# 02_LDO_and_LiPo_Circuit.net
KiCad netlist of a schematic drawn in Altium Designer
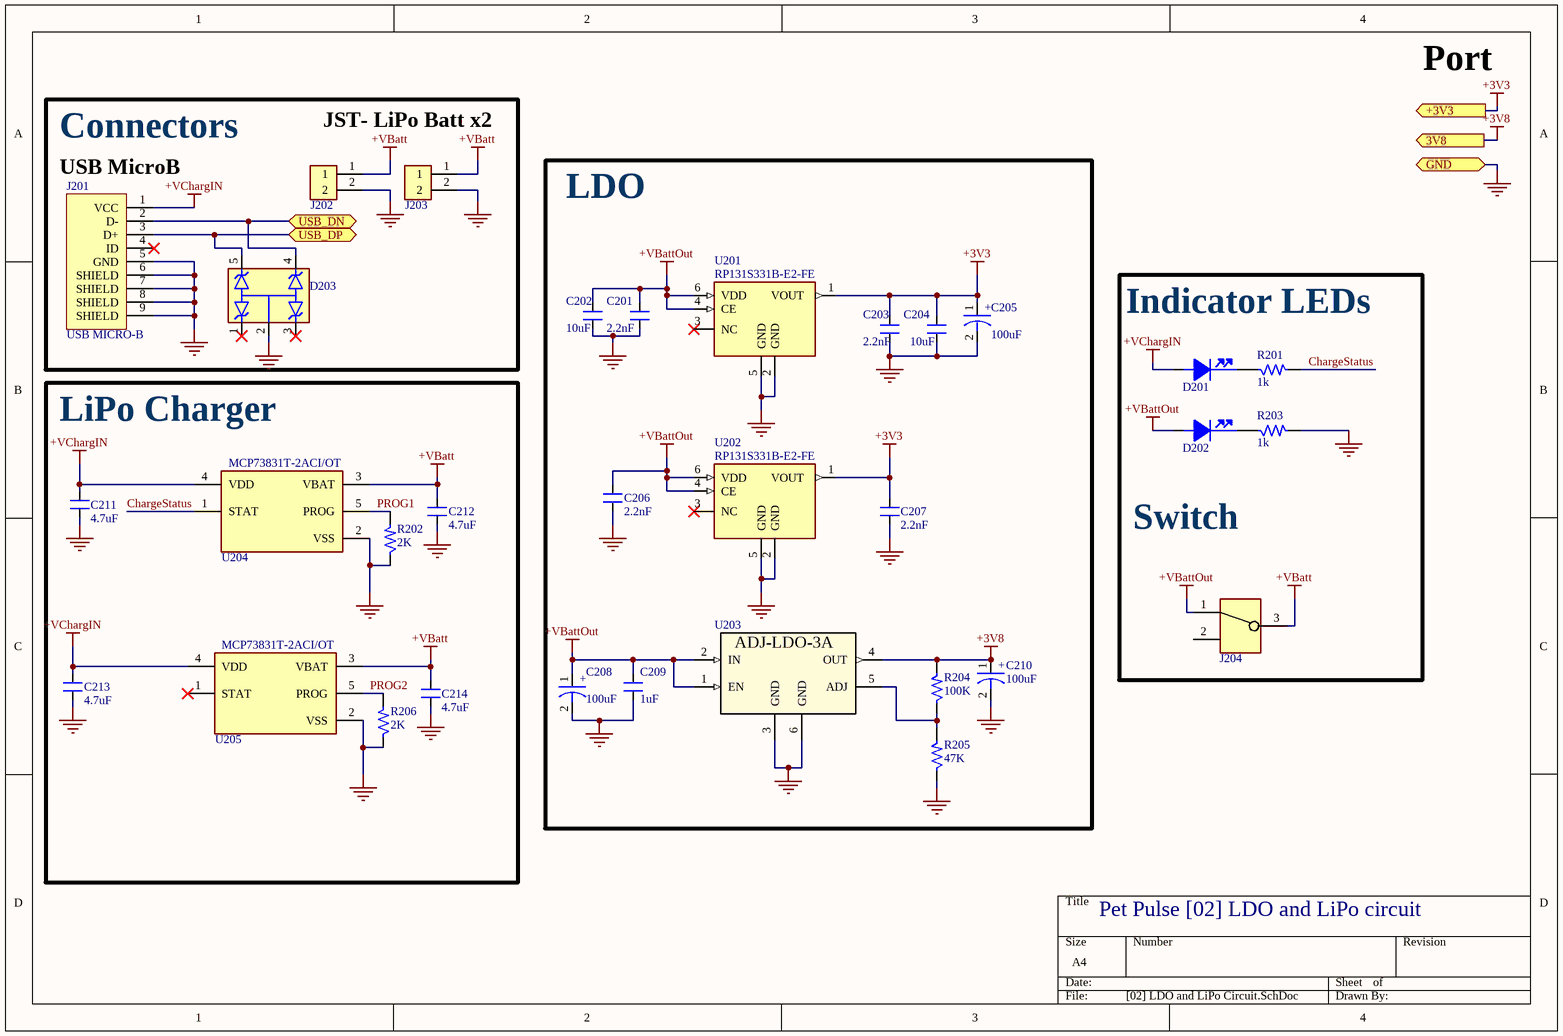
[diagram p0: [02] LDO and LiPo Circuit.SchDoc]

(export (version "E")
  (design (tool "Eeschema 10.0.6"))
  (components
    (comp (ref "C201")
      (value "2.2nF")
      (footprint "CAP_0805")
      (description "2200pF ±10% 50V Ceramic Capacitor C0G, NP0 0805 (2012 Metric)")
      (fields
        (field (name "MANUFACTURER") "YAGEO")
        (field (name "MANUFACTURER PART NUMBER") "CC0805KRX7R9BB222")
      )
      (libsource (lib "SchematicLibrary") (part "CAP_2.2nF-50V-10%-0805"))
    )
    (comp (ref "C202")
      (value "10uF")
      (footprint "CAP_1206")
      (description "10µF ±10% 50V Ceramic Capacitor X7R 1206 (3216 Metric)")
      (fields
        (field (name "MANUFACTURER") "KEMET")
        (field (name "MANUFACTURER PART NUMBER") "CL31B106KBHNNNE")
      )
      (libsource (lib "IntegratedLibraryNamanTanwar") (part "CAP_10uF-50V-10%-1206"))
    )
    (comp (ref "C203")
      (value "2.2nF")
      (footprint "CAP_0805")
      (description "2200pF ±10% 50V Ceramic Capacitor C0G, NP0 0805 (2012 Metric)")
      (fields
        (field (name "MANUFACTURER") "YAGEO")
        (field (name "MANUFACTURER PART NUMBER") "CC0805KRX7R9BB222")
      )
      (libsource (lib "SchematicLibrary") (part "CAP_2.2nF-50V-10%-0805"))
    )
    (comp (ref "C204")
      (value "10uF")
      (footprint "CAP_1206")
      (description "10µF ±10% 50V Ceramic Capacitor X7R 1206 (3216 Metric)")
      (fields
        (field (name "MANUFACTURER") "KEMET")
        (field (name "MANUFACTURER PART NUMBER") "CL31B106KBHNNNE")
      )
      (libsource (lib "IntegratedLibraryNamanTanwar") (part "CAP_10uF-50V-10%-1206"))
    )
    (comp (ref "C205")
      (value "100uF")
      (footprint "ACAP_P236_D305_H303_RAD")
      (description "100µF 25V Aluminum Electrolytic Capacitors Radial, Can - SMD 1000 Hrs @ 105°C")
      (fields
        (field (name "MANUFACTURER") "Nichicon")
        (field (name "MANUFACTURER PART NUMBER") "UWT1E101MCL1GS")
      )
      (libsource (lib "IntegratedLibraryNamanTanwar") (part "CAP-P_100uF-25V-20%-RAD"))
    )
    (comp (ref "C206")
      (value "2.2nF")
      (footprint "CAP_0805")
      (description "2200pF ±10% 50V Ceramic Capacitor C0G, NP0 0805 (2012 Metric)")
      (fields
        (field (name "MANUFACTURER") "YAGEO")
        (field (name "MANUFACTURER PART NUMBER") "CC0805KRX7R9BB222")
      )
      (libsource (lib "SchematicLibrary") (part "CAP_2.2nF-50V-10%-0805"))
    )
    (comp (ref "C207")
      (value "2.2nF")
      (footprint "CAP_0805")
      (description "2200pF ±10% 50V Ceramic Capacitor C0G, NP0 0805 (2012 Metric)")
      (fields
        (field (name "MANUFACTURER") "YAGEO")
        (field (name "MANUFACTURER PART NUMBER") "CC0805KRX7R9BB222")
      )
      (libsource (lib "SchematicLibrary") (part "CAP_2.2nF-50V-10%-0805"))
    )
    (comp (ref "C208")
      (value "100uF")
      (footprint "ACAP_P236_D305_H303_RAD")
      (description "100µF 25V Aluminum Electrolytic Capacitors Radial, Can - SMD 1000 Hrs @ 105°C")
      (fields
        (field (name "MANUFACTURER") "Nichicon")
        (field (name "MANUFACTURER PART NUMBER") "UWT1E101MCL1GS")
      )
      (libsource (lib "IntegratedLibraryNamanTanwar") (part "CAP-P_100uF-25V-20%-RAD"))
    )
    (comp (ref "C209")
      (value "1uF")
      (footprint "CAP_0805")
      (description "1µF ±5% 50V Ceramic Capacitor X7R 0805 (2012 Metric)")
      (fields
        (field (name "MANUFACTURER") "Samsung")
        (field (name "MANUFACTURER PART NUMBER") "CC0805JKX7R9BB105")
      )
      (libsource (lib "IntegratedLibraryNamanTanwar") (part "CAP_1uF-50V-5%-0805"))
    )
    (comp (ref "C210")
      (value "100uF")
      (footprint "ACAP_P236_D305_H303_RAD")
      (description "100µF 25V Aluminum Electrolytic Capacitors Radial, Can - SMD 1000 Hrs @ 105°C")
      (fields
        (field (name "MANUFACTURER") "Nichicon")
        (field (name "MANUFACTURER PART NUMBER") "UWT1E101MCL1GS")
      )
      (libsource (lib "IntegratedLibraryNamanTanwar") (part "CAP-P_100uF-25V-20%-RAD"))
    )
    (comp (ref "C211")
      (value "4.7uF")
      (footprint "CAP_0805")
      (description "4.7µF ±10% 50V Ceramic Capacitor X5R 0805 (2012 Metric)")
      (fields
        (field (name "MANUFACTURER") "Yageo")
        (field (name "MANUFACTURER PART NUMBER") "GRM21BR61H475KE51L")
      )
      (libsource (lib "IntegratedLibraryNamanTanwar") (part "CAP_4.7uF-50V-10%-0805"))
    )
    (comp (ref "C212")
      (value "4.7uF")
      (footprint "CAP_0805")
      (description "4.7µF ±10% 50V Ceramic Capacitor X5R 0805 (2012 Metric)")
      (fields
        (field (name "MANUFACTURER") "Yageo")
        (field (name "MANUFACTURER PART NUMBER") "GRM21BR61H475KE51L")
      )
      (libsource (lib "IntegratedLibraryNamanTanwar") (part "CAP_4.7uF-50V-10%-0805"))
    )
    (comp (ref "C213")
      (value "4.7uF")
      (footprint "CAP_0805")
      (description "4.7µF ±10% 50V Ceramic Capacitor X5R 0805 (2012 Metric)")
      (fields
        (field (name "MANUFACTURER") "Yageo")
        (field (name "MANUFACTURER PART NUMBER") "GRM21BR61H475KE51L")
      )
      (libsource (lib "IntegratedLibraryNamanTanwar") (part "CAP_4.7uF-50V-10%-0805"))
    )
    (comp (ref "C214")
      (value "4.7uF")
      (footprint "CAP_0805")
      (description "4.7µF ±10% 50V Ceramic Capacitor X5R 0805 (2012 Metric)")
      (fields
        (field (name "MANUFACTURER") "Yageo")
        (field (name "MANUFACTURER PART NUMBER") "GRM21BR61H475KE51L")
      )
      (libsource (lib "IntegratedLibraryNamanTanwar") (part "CAP_4.7uF-50V-10%-0805"))
    )
    (comp (ref "D201")
      (value "LED 0805 ORANGE")
      (footprint "LED_0805")
      (description "Orange LED 0805 Vf = 2V, 20mA")
      (fields
        (field (name "MANUFACTURER") "Osram Opto")
        (field (name "MANUFACTURER PART NUMBER") "LOR976-PS-1")
      )
      (libsource (lib "IntegratedLibraryNamanTanwar") (part "LED_ORANGE-2V-20mA- 0805"))
    )
    (comp (ref "D202")
      (value "LED 0805 ORANGE")
      (footprint "LED_0805")
      (description "Orange LED 0805 Vf = 2V, 20mA")
      (fields
        (field (name "MANUFACTURER") "Osram Opto")
        (field (name "MANUFACTURER PART NUMBER") "LOR976-PS-1")
      )
      (libsource (lib "IntegratedLibraryNamanTanwar") (part "LED_ORANGE-2V-20mA- 0805"))
    )
    (comp (ref "D203")
      (value "ESDA6V1W5")
      (footprint "SOT-323-5")
      (description "Tvs Diode Array 3V reverse standoff, 6.1V reverse breakdown.  SOT-323-5")
      (fields (field (name "MANUFACTURER") "STMicroelectronics"))
      (libsource (lib "IntegratedLibraryNamanTanwar") (part "DIO_TVS_ARRY_3Vrm_6.1Vbr_ESDA6V1W5"))
    )
    (comp (ref "J201")
      (value "USB MICRO-B")
      (footprint "CON_USB2.0_MICROB-SMD")
      (description "USB - micro B USB 2.0 Receptacle Connector 5 Position Surface Mount, Right Angle")
      (fields (field (name "MANUFACTURER") "ICC") (field (name "MANUFACTURER PART NUMBER") "10118192-0001LF"))
      (libsource (lib "IntegratedLibraryNamanTanwar") (part "CON_USB2.0_MICROB-SMD"))
    )
    (comp (ref "J202")
      (value "1x2 JST")
      (footprint "CON-JST-1X2-1.5-M-TH")
      (description "Connector Header Through Hole 2 position 0.059\" (1.50mm)")
      (fields
        (field (name "MANUFACTURER") "JST Sales America Inc.")
        (field (name "MANUFACTURER PART NUMBER") "B2B-ZR (LF)(SN)")
      )
      (libsource (lib "SchematicLibrary") (part "CON-JST-1X2-1.5-M-TH"))
    )
    (comp (ref "J203")
      (value "1x2 JST")
      (footprint "CON-JST-1X2-1.5-M-TH")
      (description "Connector Header Through Hole 2 position 0.059\" (1.50mm)")
      (fields
        (field (name "MANUFACTURER") "JST Sales America Inc.")
        (field (name "MANUFACTURER PART NUMBER") "B2B-ZR (LF)(SN)")
      )
      (libsource (lib "SchematicLibrary") (part "CON-JST-1X2-1.5-M-TH"))
    )
    (comp (ref "J204")
      (value "SW1_SlideSW_SMD_SPDT_450405020524")
      (footprint "SW1_SlideSW_SMD_SPDT_450405020524")
      (description "Slide Switch SPDT Surface Mount")
      (fields
        (field (name "MANUFACTURER") "Würth Elektronik")
        (field (name "MANUFACTURER PART NUMBER") "450405020524")
      )
      (libsource (lib "IntegratedLibraryNamanTanwar") (part "SW1_SlideSW_SMD_SPDT_450405020524"))
    )
    (comp (ref "R201")
      (value "1k")
      (footprint "RES_0805")
      (description "RES 1K OHM 5% 1/8W 0805")
      (fields
        (field (name "MANUFACTURER PART NUMBER") "RC0805JR-131KL")
        (field (name "MANUFACTURER") "YAGEO")
      )
      (libsource (lib "IntegratedLibraryNamanTanwar") (part "RES_1K- 0.125W-5%-0805"))
    )
    (comp (ref "R202")
      (value "2K")
      (footprint "RES_0805")
      (description "2 kOhms ±1% 0.125W, 1/8W Chip Resistor 0805 (2012 Metric) Moisture Resistant Thick Film")
      (fields
        (field (name "MANUFACTURER") "TE Connectivity")
        (field (name "MANUFACTURER PART NUMBER") "RC0805FR-072KL")
      )
      (libsource (lib "IntegratedLibraryNamanTanwar") (part "RES_2K-0.125W-1%-0805"))
    )
    (comp (ref "R203")
      (value "1k")
      (footprint "RES_0805")
      (description "RES 1K OHM 5% 1/8W 0805")
      (fields
        (field (name "MANUFACTURER PART NUMBER") "RC0805JR-131KL")
        (field (name "MANUFACTURER") "YAGEO")
      )
      (libsource (lib "IntegratedLibraryNamanTanwar") (part "RES_1K- 0.125W-5%-0805"))
    )
    (comp (ref "R204")
      (value "100K")
      (footprint "RES_0805")
      (description "100 kOhms ±1% 0.125W, 1/8W Chip Resistor 0805 (2012 Metric) Automotive AEC-Q200 Thick Film")
      (fields (field (name "MANUFACTURER") "Walsin") (field (name "MANUFACTURER PART NUMBER") "WR08X1003FTL"))
      (libsource (lib "IntegratedLibraryNamanTanwar") (part "RES_100K-0.125W-1%-0805"))
    )
    (comp (ref "R205")
      (value "47K")
      (footprint "RES_0805")
      (description "47 kOhms ±1% 0.125W, 1/8W Chip Resistor 0805 (2012 Metric) Moisture Resistant Thick Film")
      (fields
        (field (name "MANUFACTURER") "YAGEO")
        (field (name "MANUFACTURER PART NUMBER") "RC0805FR-0747KL")
      )
      (libsource (lib "IntegratedLibraryNamanTanwar") (part "RES_47K-0.125W-1%-0805"))
    )
    (comp (ref "R206")
      (value "2K")
      (footprint "RES_0805")
      (description "2 kOhms ±1% 0.125W, 1/8W Chip Resistor 0805 (2012 Metric) Moisture Resistant Thick Film")
      (fields
        (field (name "MANUFACTURER") "TE Connectivity")
        (field (name "MANUFACTURER PART NUMBER") "RC0805FR-072KL")
      )
      (libsource (lib "IntegratedLibraryNamanTanwar") (part "RES_2K-0.125W-1%-0805"))
    )
    (comp (ref "U201")
      (value "RP131S331B-E2-FE")
      (footprint "6HSOP")
      (description "LDO 3.3V Output 1A 6-HSOP-J")
      (fields (field (name "MANUFACTURER") "Nisshinbo Micro Devices Inc."))
      (libsource (lib "IntegratedLibraryNamanTanwar") (part "REG_LDO_3.3V_1A_RP131S331B-E2-FE"))
    )
    (comp (ref "U202")
      (value "RP131S331B-E2-FE")
      (footprint "6HSOP")
      (description "LDO 3.3V Output 1A 6-HSOP-J")
      (fields (field (name "MANUFACTURER") "Nisshinbo Micro Devices Inc."))
      (libsource (lib "IntegratedLibraryNamanTanwar") (part "REG_LDO_3.3V_1A_RP131S331B-E2-FE"))
    )
    (comp (ref "U203")
      (value "MIC29302AWD")
      (footprint "TO-252-5_MCH")
      (description "Linear Voltage Regulator IC Positive Adjustable 1 Output 3A TO-252-5")
      (libsource (lib "SchematicLibrary") (part "REG_LDO_ADJ_3A_MIC29302AWD"))
    )
    (comp (ref "U204")
      (value "MCP73831T-2ACI/OT")
      (footprint "SOT-23-5_MC_MCH")
      (description "Charger IC Lithium Ion/Polymer SOT-23-5")
      (fields (field (name "MANUFACTURER") "Microchip"))
      (libsource (lib "IntegratedLibraryNamanTanwar") (part "IC_BATT_CNTL_LI-ION-1CELL"))
    )
    (comp (ref "U205")
      (value "MCP73831T-2ACI/OT")
      (footprint "SOT-23-5_MC_MCH")
      (description "Charger IC Lithium Ion/Polymer SOT-23-5")
      (fields (field (name "MANUFACTURER") "Microchip"))
      (libsource (lib "IntegratedLibraryNamanTanwar") (part "IC_BATT_CNTL_LI-ION-1CELL"))
    )
  )
  (nets
    (net (code "1") (name "+3V3") (class "Default")
      (node (ref "C203") (pin "1") (pinfunction "1_1") (pintype "passive"))
      (node (ref "C204") (pin "2") (pinfunction "2_2") (pintype "passive"))
      (node (ref "C205") (pin "1") (pinfunction "1_1") (pintype "passive"))
      (node (ref "C207") (pin "1") (pinfunction "1_1") (pintype "passive"))
      (node (ref "U201") (pin "1") (pinfunction "VOUT_1") (pintype "output"))
      (node (ref "U202") (pin "1") (pinfunction "VOUT_1") (pintype "output"))
    )
    (net (code "2") (name "+3V8") (class "Default")
      (node (ref "C210") (pin "1") (pinfunction "1_1") (pintype "passive"))
      (node (ref "R204") (pin "2") (pinfunction "2_2") (pintype "passive"))
      (node (ref "U203") (pin "4") (pinfunction "OUT_4") (pintype "output"))
    )
    (net (code "3") (name "+VBatt") (class "Default")
      (node (ref "C212") (pin "2") (pinfunction "2_2") (pintype "passive"))
      (node (ref "C214") (pin "2") (pinfunction "2_2") (pintype "passive"))
      (node (ref "J202") (pin "1") (pinfunction "1_1") (pintype "passive"))
      (node (ref "J203") (pin "1") (pinfunction "1_1") (pintype "passive"))
      (node (ref "J204") (pin "3") (pinfunction "3_3") (pintype "passive"))
      (node (ref "U204") (pin "3") (pinfunction "VBAT_3") (pintype "passive"))
      (node (ref "U205") (pin "3") (pinfunction "VBAT_3") (pintype "passive"))
    )
    (net (code "4") (name "+VBattOut") (class "Default")
      (node (ref "C201") (pin "1") (pinfunction "1_1") (pintype "passive"))
      (node (ref "C202") (pin "2") (pinfunction "2_2") (pintype "passive"))
      (node (ref "C206") (pin "1") (pinfunction "1_1") (pintype "passive"))
      (node (ref "C208") (pin "1") (pinfunction "1_1") (pintype "passive"))
      (node (ref "C209") (pin "2") (pinfunction "2_2") (pintype "passive"))
      (node (ref "D202") (pin "2") (pinfunction "Anode_2") (pintype "passive"))
      (node (ref "J204") (pin "1") (pinfunction "1_1") (pintype "passive"))
      (node (ref "U201") (pin "4") (pinfunction "CE_4") (pintype "input"))
      (node (ref "U201") (pin "6") (pinfunction "VDD_6") (pintype "input"))
      (node (ref "U202") (pin "4") (pinfunction "CE_4") (pintype "input"))
      (node (ref "U202") (pin "6") (pinfunction "VDD_6") (pintype "input"))
      (node (ref "U203") (pin "1") (pinfunction "EN_1") (pintype "input"))
      (node (ref "U203") (pin "2") (pinfunction "IN_2") (pintype "input"))
    )
    (net (code "5") (name "+VChargIN") (class "Default")
      (node (ref "C211") (pin "2") (pinfunction "2_2") (pintype "passive"))
      (node (ref "C213") (pin "2") (pinfunction "2_2") (pintype "passive"))
      (node (ref "D201") (pin "2") (pinfunction "Anode_2") (pintype "passive"))
      (node (ref "J201") (pin "1") (pinfunction "VCC_1") (pintype "passive"))
      (node (ref "U204") (pin "4") (pinfunction "VDD_4") (pintype "passive"))
      (node (ref "U205") (pin "4") (pinfunction "VDD_4") (pintype "passive"))
    )
    (net (code "6") (name "/ChargeStatus") (class "Default")
      (node (ref "R201") (pin "2") (pinfunction "2_2") (pintype "passive"))
      (node (ref "U204") (pin "1") (pinfunction "STAT_1") (pintype "passive"))
    )
    (net (code "7") (name "/PROG1") (class "Default")
      (node (ref "R202") (pin "2") (pinfunction "2_2") (pintype "passive"))
      (node (ref "U204") (pin "5") (pinfunction "PROG_5") (pintype "passive"))
    )
    (net (code "8") (name "/PROG2") (class "Default")
      (node (ref "R206") (pin "2") (pinfunction "2_2") (pintype "passive"))
      (node (ref "U205") (pin "5") (pinfunction "PROG_5") (pintype "passive"))
    )
    (net (code "9") (name "/USB_DN") (class "Default")
      (node (ref "D203") (pin "4") (pinfunction "4_4") (pintype "passive"))
      (node (ref "J201") (pin "2") (pinfunction "D-_2") (pintype "passive"))
    )
    (net (code "10") (name "/USB_DP") (class "Default")
      (node (ref "D203") (pin "5") (pinfunction "5_5") (pintype "passive"))
      (node (ref "J201") (pin "3") (pinfunction "D+_3") (pintype "passive"))
    )
    (net (code "11") (name "GND") (class "Default")
      (node (ref "C201") (pin "2") (pinfunction "2_2") (pintype "passive"))
      (node (ref "C202") (pin "1") (pinfunction "1_1") (pintype "passive"))
      (node (ref "C203") (pin "2") (pinfunction "2_2") (pintype "passive"))
      (node (ref "C204") (pin "1") (pinfunction "1_1") (pintype "passive"))
      (node (ref "C205") (pin "2") (pinfunction "2_2") (pintype "passive"))
      (node (ref "C206") (pin "2") (pinfunction "2_2") (pintype "passive"))
      (node (ref "C207") (pin "2") (pinfunction "2_2") (pintype "passive"))
      (node (ref "C208") (pin "2") (pinfunction "2_2") (pintype "passive"))
      (node (ref "C209") (pin "1") (pinfunction "1_1") (pintype "passive"))
      (node (ref "C210") (pin "2") (pinfunction "2_2") (pintype "passive"))
      (node (ref "C211") (pin "1") (pinfunction "1_1") (pintype "passive"))
      (node (ref "C212") (pin "1") (pinfunction "1_1") (pintype "passive"))
      (node (ref "C213") (pin "1") (pinfunction "1_1") (pintype "passive"))
      (node (ref "C214") (pin "1") (pinfunction "1_1") (pintype "passive"))
      (node (ref "D203") (pin "2") (pinfunction "2_2") (pintype "passive"))
      (node (ref "J201") (pin "5") (pinfunction "GND_5") (pintype "passive"))
      (node (ref "J201") (pin "6") (pinfunction "SHIELD_6") (pintype "passive"))
      (node (ref "J201") (pin "7") (pinfunction "SHIELD_7") (pintype "passive"))
      (node (ref "J201") (pin "8") (pinfunction "SHIELD_8") (pintype "passive"))
      (node (ref "J201") (pin "9") (pinfunction "SHIELD_9") (pintype "passive"))
      (node (ref "J202") (pin "2") (pinfunction "2_2") (pintype "passive"))
      (node (ref "J203") (pin "2") (pinfunction "2_2") (pintype "passive"))
      (node (ref "R202") (pin "1") (pinfunction "1_1") (pintype "passive"))
      (node (ref "R203") (pin "2") (pinfunction "2_2") (pintype "passive"))
      (node (ref "R205") (pin "1") (pinfunction "1_1") (pintype "passive"))
      (node (ref "R206") (pin "1") (pinfunction "1_1") (pintype "passive"))
      (node (ref "U201") (pin "2") (pinfunction "GND_2") (pintype "passive"))
      (node (ref "U201") (pin "5") (pinfunction "GND_5") (pintype "passive"))
      (node (ref "U202") (pin "2") (pinfunction "GND_2") (pintype "passive"))
      (node (ref "U202") (pin "5") (pinfunction "GND_5") (pintype "passive"))
      (node (ref "U203") (pin "3") (pinfunction "GND_3") (pintype "power_in"))
      (node (ref "U203") (pin "6") (pinfunction "GND_6") (pintype "power_in"))
      (node (ref "U204") (pin "2") (pinfunction "VSS_2") (pintype "passive"))
      (node (ref "U205") (pin "2") (pinfunction "VSS_2") (pintype "passive"))
    )
    (net (code "12") (name "Net-(D201-Cathode)") (class "Default")
      (node (ref "D201") (pin "1") (pinfunction "Cathode_1") (pintype "passive"))
      (node (ref "R201") (pin "1") (pinfunction "1_1") (pintype "passive"))
    )
    (net (code "13") (name "Net-(D202-Cathode)") (class "Default")
      (node (ref "D202") (pin "1") (pinfunction "Cathode_1") (pintype "passive"))
      (node (ref "R203") (pin "1") (pinfunction "1_1") (pintype "passive"))
    )
    (net (code "14") (name "Net-(U203-ADJ)") (class "Default")
      (node (ref "R204") (pin "1") (pinfunction "1_1") (pintype "passive"))
      (node (ref "R205") (pin "2") (pinfunction "2_2") (pintype "passive"))
      (node (ref "U203") (pin "5") (pinfunction "ADJ_5") (pintype "passive"))
    )
    (net (code "15") (name "unconnected-(D203-Pad1)") (class "Default")
      (node (ref "D203") (pin "1") (pinfunction "1_1") (pintype "passive+no_connect"))
    )
    (net (code "16") (name "unconnected-(D203-Pad3)") (class "Default")
      (node (ref "D203") (pin "3") (pinfunction "3_3") (pintype "passive+no_connect"))
    )
    (net (code "17") (name "unconnected-(J201-ID-Pad4)") (class "Default")
      (node (ref "J201") (pin "4") (pinfunction "ID_4") (pintype "passive+no_connect"))
    )
    (net (code "18") (name "unconnected-(J204-Pad2)") (class "Default")
      (node (ref "J204") (pin "2") (pinfunction "2_2") (pintype "passive"))
    )
    (net (code "19") (name "unconnected-(U201-NC-Pad3)") (class "Default")
      (node (ref "U201") (pin "3") (pinfunction "NC_3") (pintype "passive+no_connect"))
    )
    (net (code "20") (name "unconnected-(U202-NC-Pad3)") (class "Default")
      (node (ref "U202") (pin "3") (pinfunction "NC_3") (pintype "passive+no_connect"))
    )
    (net (code "21") (name "unconnected-(U205-STAT-Pad1)") (class "Default")
      (node (ref "U205") (pin "1") (pinfunction "STAT_1") (pintype "passive+no_connect"))
    )
  )
)
